# sistema_min.net
KiCad netlist of a schematic drawn in EAGLE
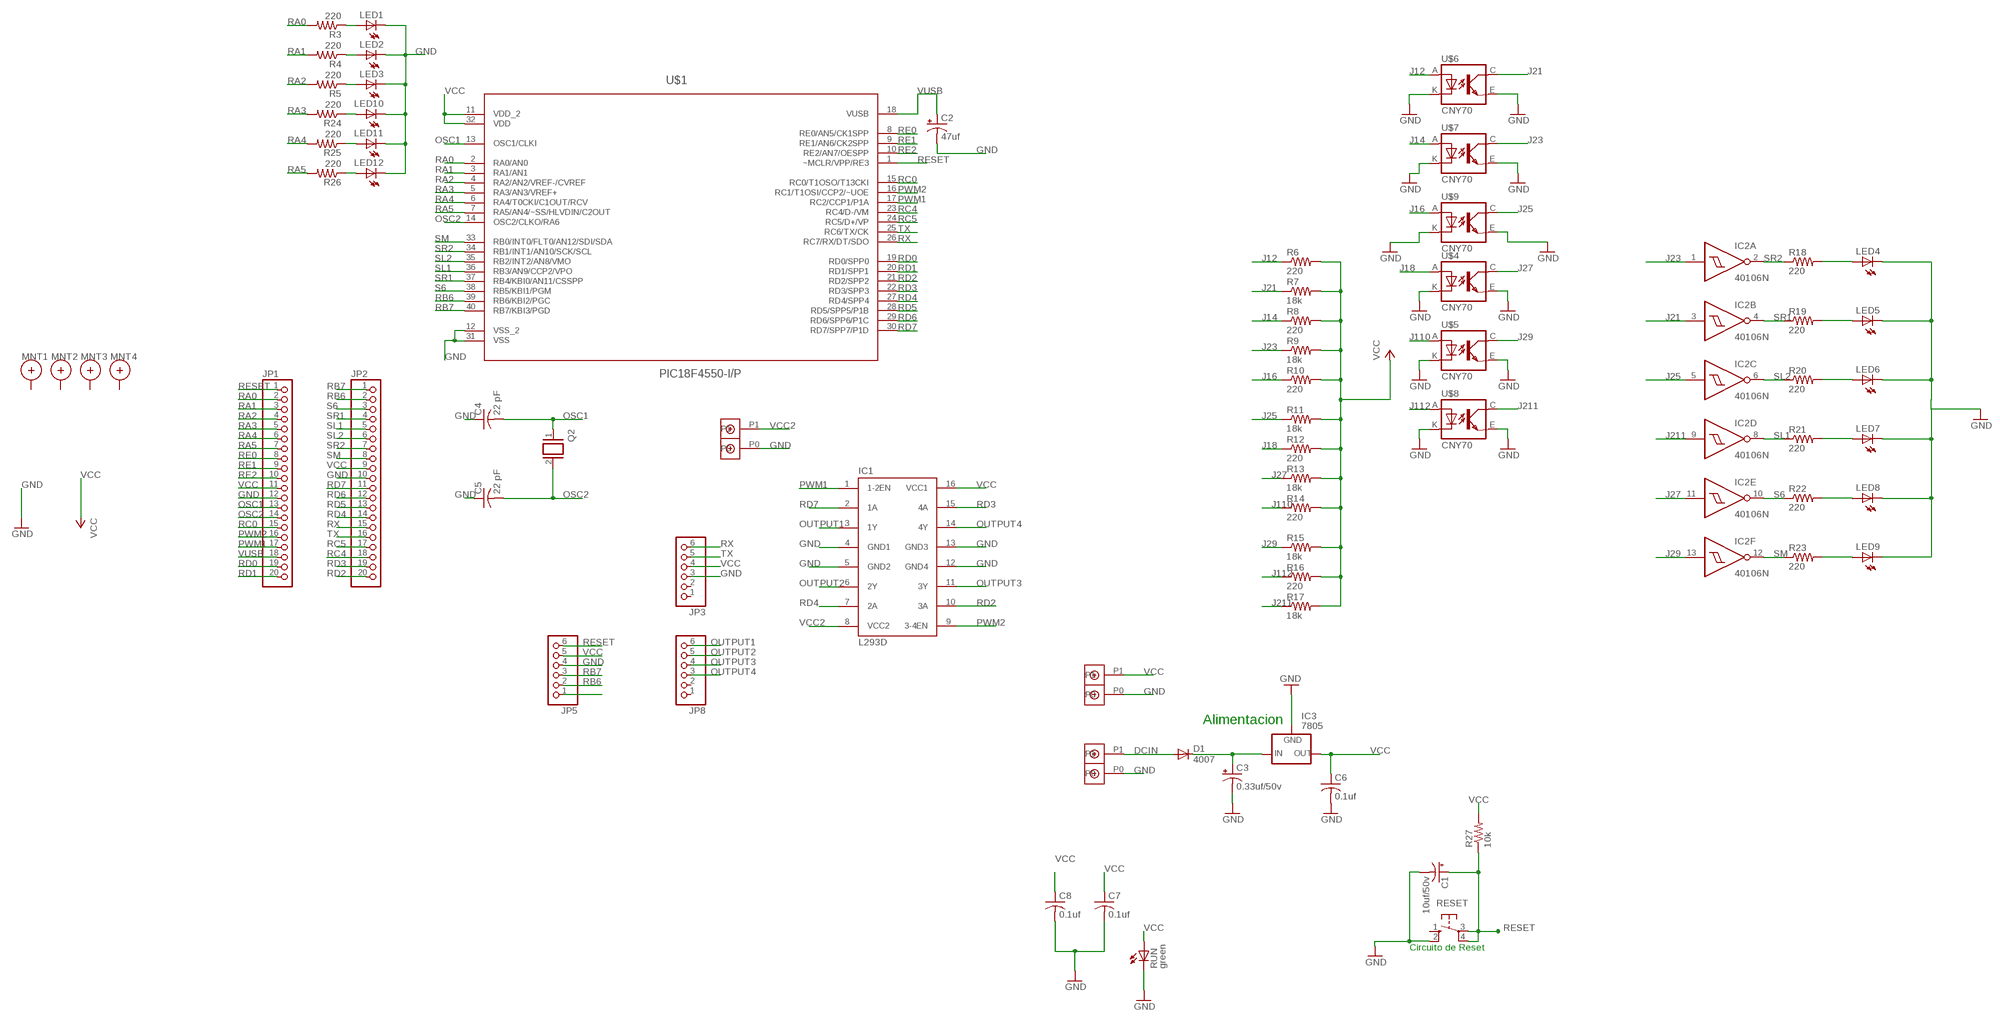
[diagram p0: schematic, sheet 1]

(export (version "E")
  (design (tool "Eeschema 10.0.6"))
  (components
    (comp (ref "C1")
      (value "10uf/50v")
      (footprint "eagle-import:153CLV-0505")
      (libsource (lib "eagle-import") (part "CPOL-US153CLV-0505"))
    )
    (comp (ref "C2")
      (value "47uf")
      (footprint "eagle-import:153CLV-0605")
      (libsource (lib "eagle-import") (part "CPOL-US153CLV-0605"))
    )
    (comp (ref "C3")
      (value "0.33uf/50v")
      (footprint "eagle-import:153CLV-0405")
      (libsource (lib "eagle-import") (part "CPOL-US153CLV-0405"))
    )
    (comp (ref "C4")
      (value "22 pF")
      (footprint "eagle-import:C1206")
      (libsource (lib "eagle-import") (part "C-USC1206"))
    )
    (comp (ref "C5")
      (value "22 pF")
      (footprint "eagle-import:C1206")
      (libsource (lib "eagle-import") (part "C-USC1206"))
    )
    (comp (ref "C6")
      (value "0.1uf")
      (footprint "eagle-import:C1206")
      (libsource (lib "eagle-import") (part "C-USC1206"))
    )
    (comp (ref "C7")
      (value "0.1uf")
      (footprint "eagle-import:C1206")
      (libsource (lib "eagle-import") (part "C-USC1206"))
    )
    (comp (ref "C8")
      (value "0.1uf")
      (footprint "eagle-import:C1206")
      (libsource (lib "eagle-import") (part "C-USC1206"))
    )
    (comp (ref "D1")
      (value "4007")
      (footprint "eagle-import:DO35-7")
      (libsource (lib "eagle-import") (part "1N4148DO35-7"))
    )
    (comp (ref "IC1")
      (value "L293D")
      (footprint "eagle-import:DIL16")
      (libsource (lib "eagle-import") (part "L293D"))
    )
    (comp (ref "IC2")
      (value "40106N")
      (footprint "eagle-import:DIL14")
      (libsource (lib "eagle-import") (part "40106N"))
    )
    (comp (ref "IC3")
      (value "7805")
      (footprint "eagle-import:79XXS")
      (libsource (lib "eagle-import") (part "79XXS"))
    )
    (comp (ref "JP1")
      (value "PINHD-1X20")
      (footprint "eagle-import:1X20")
      (libsource (lib "eagle-import") (part "PINHD-1X20"))
    )
    (comp (ref "JP2")
      (value "PINHD-1X20")
      (footprint "eagle-import:1X20")
      (libsource (lib "eagle-import") (part "PINHD-1X20"))
    )
    (comp (ref "JP3")
      (value "PINHD-1X6")
      (footprint "eagle-import:1X06")
      (libsource (lib "eagle-import") (part "PINHD-1X6"))
    )
    (comp (ref "JP5")
      (value "PINHD-1X6")
      (footprint "eagle-import:1X06")
      (libsource (lib "eagle-import") (part "PINHD-1X6"))
    )
    (comp (ref "JP8")
      (value "PINHD-1X6")
      (footprint "eagle-import:1X06")
      (libsource (lib "eagle-import") (part "PINHD-1X6"))
    )
    (comp (ref "LED1")
      (value "LEDCHIPLED_1206")
      (footprint "eagle-import:CHIPLED_1206")
      (libsource (lib "eagle-import") (part "LEDCHIPLED_1206"))
    )
    (comp (ref "LED2")
      (value "LEDCHIPLED_1206")
      (footprint "eagle-import:CHIPLED_1206")
      (libsource (lib "eagle-import") (part "LEDCHIPLED_1206"))
    )
    (comp (ref "LED3")
      (value "LEDCHIPLED_1206")
      (footprint "eagle-import:CHIPLED_1206")
      (libsource (lib "eagle-import") (part "LEDCHIPLED_1206"))
    )
    (comp (ref "LED4")
      (value "LEDCHIPLED_1206")
      (footprint "eagle-import:CHIPLED_1206")
      (libsource (lib "eagle-import") (part "LEDCHIPLED_1206"))
    )
    (comp (ref "LED5")
      (value "LEDCHIPLED_1206")
      (footprint "eagle-import:CHIPLED_1206")
      (libsource (lib "eagle-import") (part "LEDCHIPLED_1206"))
    )
    (comp (ref "LED6")
      (value "LEDCHIPLED_1206")
      (footprint "eagle-import:CHIPLED_1206")
      (libsource (lib "eagle-import") (part "LEDCHIPLED_1206"))
    )
    (comp (ref "LED7")
      (value "LEDCHIPLED_1206")
      (footprint "eagle-import:CHIPLED_1206")
      (libsource (lib "eagle-import") (part "LEDCHIPLED_1206"))
    )
    (comp (ref "LED8")
      (value "LEDCHIPLED_1206")
      (footprint "eagle-import:CHIPLED_1206")
      (libsource (lib "eagle-import") (part "LEDCHIPLED_1206"))
    )
    (comp (ref "LED9")
      (value "LEDCHIPLED_1206")
      (footprint "eagle-import:CHIPLED_1206")
      (libsource (lib "eagle-import") (part "LEDCHIPLED_1206"))
    )
    (comp (ref "LED10")
      (value "LEDCHIPLED_1206")
      (footprint "eagle-import:CHIPLED_1206")
      (libsource (lib "eagle-import") (part "LEDCHIPLED_1206"))
    )
    (comp (ref "LED11")
      (value "LEDCHIPLED_1206")
      (footprint "eagle-import:CHIPLED_1206")
      (libsource (lib "eagle-import") (part "LEDCHIPLED_1206"))
    )
    (comp (ref "LED12")
      (value "LEDCHIPLED_1206")
      (footprint "eagle-import:CHIPLED_1206")
      (libsource (lib "eagle-import") (part "LEDCHIPLED_1206"))
    )
    (comp (ref "MNT1")
      (value "HOLE_MNT_0.135")
      (footprint "eagle-import:HOLE_MNT_#5-40")
      (libsource (lib "eagle-import") (part "HOLE_MNT_0.135"))
    )
    (comp (ref "MNT2")
      (value "HOLE_MNT_0.135")
      (footprint "eagle-import:HOLE_MNT_#5-40")
      (libsource (lib "eagle-import") (part "HOLE_MNT_0.135"))
    )
    (comp (ref "MNT3")
      (value "HOLE_MNT_0.135")
      (footprint "eagle-import:HOLE_MNT_#5-40")
      (libsource (lib "eagle-import") (part "HOLE_MNT_0.135"))
    )
    (comp (ref "MNT4")
      (value "HOLE_MNT_0.135")
      (footprint "eagle-import:HOLE_MNT_#5-40")
      (libsource (lib "eagle-import") (part "HOLE_MNT_0.135"))
    )
    (comp (ref "Q2")
      (value "XTAL/S")
      (footprint "eagle-import:QS")
      (libsource (lib "eagle-import") (part "XTAL/S"))
    )
    (comp (ref "R3")
      (value "220")
      (footprint "eagle-import:M1206")
      (libsource (lib "eagle-import") (part "R-US_M1206"))
    )
    (comp (ref "R4")
      (value "220")
      (footprint "eagle-import:M1206")
      (libsource (lib "eagle-import") (part "R-US_M1206"))
    )
    (comp (ref "R5")
      (value "220")
      (footprint "eagle-import:M1206")
      (libsource (lib "eagle-import") (part "R-US_M1206"))
    )
    (comp (ref "R6")
      (value "220")
      (footprint "eagle-import:M1206")
      (libsource (lib "eagle-import") (part "R-US_M1206"))
    )
    (comp (ref "R7")
      (value "18k")
      (footprint "eagle-import:M1206")
      (libsource (lib "eagle-import") (part "R-US_M1206"))
    )
    (comp (ref "R8")
      (value "220")
      (footprint "eagle-import:M1206")
      (libsource (lib "eagle-import") (part "R-US_M1206"))
    )
    (comp (ref "R9")
      (value "18k")
      (footprint "eagle-import:M1206")
      (libsource (lib "eagle-import") (part "R-US_M1206"))
    )
    (comp (ref "R10")
      (value "220")
      (footprint "eagle-import:M1206")
      (libsource (lib "eagle-import") (part "R-US_M1206"))
    )
    (comp (ref "R11")
      (value "18k")
      (footprint "eagle-import:M1206")
      (libsource (lib "eagle-import") (part "R-US_M1206"))
    )
    (comp (ref "R12")
      (value "220")
      (footprint "eagle-import:M1206")
      (libsource (lib "eagle-import") (part "R-US_M1206"))
    )
    (comp (ref "R13")
      (value "18k")
      (footprint "eagle-import:M1206")
      (libsource (lib "eagle-import") (part "R-US_M1206"))
    )
    (comp (ref "R14")
      (value "220")
      (footprint "eagle-import:M1206")
      (libsource (lib "eagle-import") (part "R-US_M1206"))
    )
    (comp (ref "R15")
      (value "18k")
      (footprint "eagle-import:M1206")
      (libsource (lib "eagle-import") (part "R-US_M1206"))
    )
    (comp (ref "R16")
      (value "220")
      (footprint "eagle-import:M1206")
      (libsource (lib "eagle-import") (part "R-US_M1206"))
    )
    (comp (ref "R17")
      (value "18k")
      (footprint "eagle-import:M1206")
      (libsource (lib "eagle-import") (part "R-US_M1206"))
    )
    (comp (ref "R18")
      (value "220")
      (footprint "eagle-import:M1206")
      (libsource (lib "eagle-import") (part "R-US_M1206"))
    )
    (comp (ref "R19")
      (value "220")
      (footprint "eagle-import:M1206")
      (libsource (lib "eagle-import") (part "R-US_M1206"))
    )
    (comp (ref "R20")
      (value "220")
      (footprint "eagle-import:M1206")
      (libsource (lib "eagle-import") (part "R-US_M1206"))
    )
    (comp (ref "R21")
      (value "220")
      (footprint "eagle-import:M1206")
      (libsource (lib "eagle-import") (part "R-US_M1206"))
    )
    (comp (ref "R22")
      (value "220")
      (footprint "eagle-import:M1206")
      (libsource (lib "eagle-import") (part "R-US_M1206"))
    )
    (comp (ref "R23")
      (value "220")
      (footprint "eagle-import:M1206")
      (libsource (lib "eagle-import") (part "R-US_M1206"))
    )
    (comp (ref "R24")
      (value "220")
      (footprint "eagle-import:M1206")
      (libsource (lib "eagle-import") (part "R-US_M1206"))
    )
    (comp (ref "R25")
      (value "220")
      (footprint "eagle-import:M1206")
      (libsource (lib "eagle-import") (part "R-US_M1206"))
    )
    (comp (ref "R26")
      (value "220")
      (footprint "eagle-import:M1206")
      (libsource (lib "eagle-import") (part "R-US_M1206"))
    )
    (comp (ref "R27")
      (value "10k")
      (footprint "eagle-import:R1206")
      (libsource (lib "eagle-import") (part "R-US_R1206"))
    )
    (comp (ref "RESET")
      (value "10-XX")
      (footprint "eagle-import:B3F-10XX")
      (fields (field (name "MPN") "B3F-1000"))
      (libsource (lib "eagle-import") (part "10-XX"))
    )
    (comp (ref "RUN")
      (value "green")
      (footprint "eagle-import:SML1206")
      (libsource (lib "eagle-import") (part "LEDSML1206"))
    )
    (comp (ref "U$1")
      (value "PIC18F4550-I/P")
      (footprint "eagle-import:DIP254P1524X635-40")
      (libsource (lib "eagle-import") (part "PIC18F4550-I/P"))
    )
    (comp (ref "U$2")
      (value "DBCONN-1X2")
      (footprint "eagle-import:DBCONN-1X2")
      (libsource (lib "eagle-import") (part "DBCONN-1X2"))
    )
    (comp (ref "U$3")
      (value "DBCONN-1X2")
      (footprint "eagle-import:DBCONN-1X2")
      (libsource (lib "eagle-import") (part "DBCONN-1X2"))
    )
    (comp (ref "U$4")
      (value "CNY70")
      (footprint "eagle-import:4")
      (libsource (lib "eagle-import") (part "CNY70"))
    )
    (comp (ref "U$5")
      (value "CNY70")
      (footprint "eagle-import:4")
      (libsource (lib "eagle-import") (part "CNY70"))
    )
    (comp (ref "U$6")
      (value "CNY70")
      (footprint "eagle-import:4")
      (libsource (lib "eagle-import") (part "CNY70"))
    )
    (comp (ref "U$7")
      (value "CNY70")
      (footprint "eagle-import:4")
      (libsource (lib "eagle-import") (part "CNY70"))
    )
    (comp (ref "U$8")
      (value "CNY70")
      (footprint "eagle-import:4")
      (libsource (lib "eagle-import") (part "CNY70"))
    )
    (comp (ref "U$9")
      (value "CNY70")
      (footprint "eagle-import:4")
      (libsource (lib "eagle-import") (part "CNY70"))
    )
    (comp (ref "U$10")
      (value "DBCONN-1X2")
      (footprint "eagle-import:DBCONN-1X2")
      (libsource (lib "eagle-import") (part "DBCONN-1X2"))
    )
  )
  (nets
    (net (code "1") (name "/DCIN") (class "Default")
      (node (ref "D1") (pin "A") (pinfunction "A_A") (pintype "passive"))
      (node (ref "U$2") (pin "P1") (pinfunction "P1_P1") (pintype "bidirectional"))
    )
    (net (code "2") (name "/J12") (class "Default")
      (node (ref "R6") (pin "1") (pinfunction "1_1") (pintype "passive"))
      (node (ref "U$6") (pin "A") (pinfunction "A_A") (pintype "passive"))
    )
    (net (code "3") (name "/J14") (class "Default")
      (node (ref "R8") (pin "1") (pinfunction "1_1") (pintype "passive"))
      (node (ref "U$7") (pin "A") (pinfunction "A_A") (pintype "passive"))
    )
    (net (code "4") (name "/J16") (class "Default")
      (node (ref "R10") (pin "1") (pinfunction "1_1") (pintype "passive"))
      (node (ref "U$9") (pin "A") (pinfunction "A_A") (pintype "passive"))
    )
    (net (code "5") (name "/J18") (class "Default")
      (node (ref "R12") (pin "1") (pinfunction "1_1") (pintype "passive"))
      (node (ref "U$4") (pin "A") (pinfunction "A_A") (pintype "passive"))
    )
    (net (code "6") (name "/J21") (class "Default")
      (node (ref "IC2") (pin "3") (pinfunction "I_3") (pintype "input"))
      (node (ref "R7") (pin "1") (pinfunction "1_1") (pintype "passive"))
      (node (ref "U$6") (pin "C") (pinfunction "COL_C") (pintype "passive"))
    )
    (net (code "7") (name "/J23") (class "Default")
      (node (ref "IC2") (pin "1") (pinfunction "I_1") (pintype "input"))
      (node (ref "R9") (pin "1") (pinfunction "1_1") (pintype "passive"))
      (node (ref "U$7") (pin "C") (pinfunction "COL_C") (pintype "passive"))
    )
    (net (code "8") (name "/J25") (class "Default")
      (node (ref "IC2") (pin "5") (pinfunction "I_5") (pintype "input"))
      (node (ref "R11") (pin "1") (pinfunction "1_1") (pintype "passive"))
      (node (ref "U$9") (pin "C") (pinfunction "COL_C") (pintype "passive"))
    )
    (net (code "9") (name "/J27") (class "Default")
      (node (ref "IC2") (pin "11") (pinfunction "I_11") (pintype "input"))
      (node (ref "R13") (pin "1") (pinfunction "1_1") (pintype "passive"))
      (node (ref "U$4") (pin "C") (pinfunction "COL_C") (pintype "passive"))
    )
    (net (code "10") (name "/J29") (class "Default")
      (node (ref "IC2") (pin "13") (pinfunction "I_13") (pintype "input"))
      (node (ref "R15") (pin "1") (pinfunction "1_1") (pintype "passive"))
      (node (ref "U$5") (pin "C") (pinfunction "COL_C") (pintype "passive"))
    )
    (net (code "11") (name "/J110") (class "Default")
      (node (ref "R14") (pin "1") (pinfunction "1_1") (pintype "passive"))
      (node (ref "U$5") (pin "A") (pinfunction "A_A") (pintype "passive"))
    )
    (net (code "12") (name "/J112") (class "Default")
      (node (ref "R16") (pin "1") (pinfunction "1_1") (pintype "passive"))
      (node (ref "U$8") (pin "A") (pinfunction "A_A") (pintype "passive"))
    )
    (net (code "13") (name "/J211") (class "Default")
      (node (ref "IC2") (pin "9") (pinfunction "I_9") (pintype "input"))
      (node (ref "R17") (pin "1") (pinfunction "1_1") (pintype "passive"))
      (node (ref "U$8") (pin "C") (pinfunction "COL_C") (pintype "passive"))
    )
    (net (code "14") (name "/OSC1") (class "Default")
      (node (ref "C4") (pin "2") (pinfunction "2_2") (pintype "passive"))
      (node (ref "JP1") (pin "13") (pinfunction "13_13") (pintype "passive"))
      (node (ref "Q2") (pin "1") (pinfunction "1_1") (pintype "passive"))
      (node (ref "U$1") (pin "13") (pinfunction "OSC1/CLKI_13") (pintype "input"))
    )
    (net (code "15") (name "/OSC2") (class "Default")
      (node (ref "C5") (pin "2") (pinfunction "2_2") (pintype "passive"))
      (node (ref "JP1") (pin "14") (pinfunction "14_14") (pintype "passive"))
      (node (ref "Q2") (pin "2") (pinfunction "2_2") (pintype "passive"))
      (node (ref "U$1") (pin "14") (pinfunction "OSC2/CLKO/RA6_14") (pintype "bidirectional"))
    )
    (net (code "16") (name "/OUTPUT1") (class "Default")
      (node (ref "IC1") (pin "3") (pinfunction "1Y_3") (pintype "output"))
      (node (ref "JP8") (pin "6") (pinfunction "6_6") (pintype "passive"))
    )
    (net (code "17") (name "/OUTPUT2") (class "Default")
      (node (ref "IC1") (pin "6") (pinfunction "2Y_6") (pintype "output"))
      (node (ref "JP8") (pin "5") (pinfunction "5_5") (pintype "passive"))
    )
    (net (code "18") (name "/OUTPUT3") (class "Default")
      (node (ref "IC1") (pin "11") (pinfunction "3Y_11") (pintype "output"))
      (node (ref "JP8") (pin "4") (pinfunction "4_4") (pintype "passive"))
    )
    (net (code "19") (name "/OUTPUT4") (class "Default")
      (node (ref "IC1") (pin "14") (pinfunction "4Y_14") (pintype "output"))
      (node (ref "JP8") (pin "3") (pinfunction "3_3") (pintype "passive"))
    )
    (net (code "20") (name "/PWM1") (class "Default")
      (node (ref "IC1") (pin "1") (pinfunction "1-2EN_1") (pintype "input"))
      (node (ref "JP1") (pin "17") (pinfunction "17_17") (pintype "passive"))
      (node (ref "U$1") (pin "17") (pinfunction "RC2/CCP1/P1A_17") (pintype "bidirectional"))
    )
    (net (code "21") (name "/PWM2") (class "Default")
      (node (ref "IC1") (pin "9") (pinfunction "3-4EN_9") (pintype "input"))
      (node (ref "JP1") (pin "16") (pinfunction "16_16") (pintype "passive"))
      (node (ref "U$1") (pin "16") (pinfunction "RC1/T1OSI/CCP2/~{UOE}_16") (pintype "bidirectional"))
    )
    (net (code "22") (name "/RA0") (class "Default")
      (node (ref "JP1") (pin "2") (pinfunction "2_2") (pintype "passive"))
      (node (ref "R3") (pin "2") (pinfunction "2_2") (pintype "passive"))
      (node (ref "U$1") (pin "2") (pinfunction "RA0/AN0_2") (pintype "bidirectional"))
    )
    (net (code "23") (name "/RA1") (class "Default")
      (node (ref "JP1") (pin "3") (pinfunction "3_3") (pintype "passive"))
      (node (ref "R4") (pin "2") (pinfunction "2_2") (pintype "passive"))
      (node (ref "U$1") (pin "3") (pinfunction "RA1/AN1_3") (pintype "bidirectional"))
    )
    (net (code "24") (name "/RA2") (class "Default")
      (node (ref "JP1") (pin "4") (pinfunction "4_4") (pintype "passive"))
      (node (ref "R5") (pin "2") (pinfunction "2_2") (pintype "passive"))
      (node (ref "U$1") (pin "4") (pinfunction "RA2/AN2/VREF-/CVREF_4") (pintype "bidirectional"))
    )
    (net (code "25") (name "/RA3") (class "Default")
      (node (ref "JP1") (pin "5") (pinfunction "5_5") (pintype "passive"))
      (node (ref "R24") (pin "2") (pinfunction "2_2") (pintype "passive"))
      (node (ref "U$1") (pin "5") (pinfunction "RA3/AN3/VREF+_5") (pintype "bidirectional"))
    )
    (net (code "26") (name "/RA4") (class "Default")
      (node (ref "JP1") (pin "6") (pinfunction "6_6") (pintype "passive"))
      (node (ref "R25") (pin "2") (pinfunction "2_2") (pintype "passive"))
      (node (ref "U$1") (pin "6") (pinfunction "RA4/T0CKI/C1OUT/RCV_6") (pintype "bidirectional"))
    )
    (net (code "27") (name "/RA5") (class "Default")
      (node (ref "JP1") (pin "7") (pinfunction "7_7") (pintype "passive"))
      (node (ref "R26") (pin "2") (pinfunction "2_2") (pintype "passive"))
      (node (ref "U$1") (pin "7") (pinfunction "RA5/AN4/~{SS/HLVDIN/C2OUT}_7") (pintype "bidirectional"))
    )
    (net (code "28") (name "/RB6") (class "Default")
      (node (ref "JP2") (pin "2") (pinfunction "2_2") (pintype "passive"))
      (node (ref "JP5") (pin "2") (pinfunction "2_2") (pintype "passive"))
      (node (ref "U$1") (pin "39") (pinfunction "RB6/KBI2/PGC_39") (pintype "bidirectional"))
    )
    (net (code "29") (name "/RB7") (class "Default")
      (node (ref "JP2") (pin "1") (pinfunction "1_1") (pintype "passive"))
      (node (ref "JP5") (pin "3") (pinfunction "3_3") (pintype "passive"))
      (node (ref "U$1") (pin "40") (pinfunction "RB7/KBI3/PGD_40") (pintype "bidirectional"))
    )
    (net (code "30") (name "/RC0") (class "Default")
      (node (ref "JP1") (pin "15") (pinfunction "15_15") (pintype "passive"))
      (node (ref "U$1") (pin "15") (pinfunction "RC0/T1OSO/T13CKI_15") (pintype "bidirectional"))
    )
    (net (code "31") (name "/RC4") (class "Default")
      (node (ref "JP2") (pin "18") (pinfunction "18_18") (pintype "passive"))
      (node (ref "U$1") (pin "23") (pinfunction "RC4/D-/VM_23") (pintype "bidirectional"))
    )
    (net (code "32") (name "/RC5") (class "Default")
      (node (ref "JP2") (pin "17") (pinfunction "17_17") (pintype "passive"))
      (node (ref "U$1") (pin "24") (pinfunction "RC5/D+/VP_24") (pintype "bidirectional"))
    )
    (net (code "33") (name "/RD0") (class "Default")
      (node (ref "JP1") (pin "19") (pinfunction "19_19") (pintype "passive"))
      (node (ref "U$1") (pin "19") (pinfunction "RD0/SPP0_19") (pintype "bidirectional"))
    )
    (net (code "34") (name "/RD1") (class "Default")
      (node (ref "JP1") (pin "20") (pinfunction "20_20") (pintype "passive"))
      (node (ref "U$1") (pin "20") (pinfunction "RD1/SPP1_20") (pintype "bidirectional"))
    )
    (net (code "35") (name "/RD2") (class "Default")
      (node (ref "IC1") (pin "10") (pinfunction "3A_10") (pintype "input"))
      (node (ref "JP2") (pin "20") (pinfunction "20_20") (pintype "passive"))
      (node (ref "U$1") (pin "21") (pinfunction "RD2/SPP2_21") (pintype "bidirectional"))
    )
    (net (code "36") (name "/RD3") (class "Default")
      (node (ref "IC1") (pin "15") (pinfunction "4A_15") (pintype "input"))
      (node (ref "JP2") (pin "19") (pinfunction "19_19") (pintype "passive"))
      (node (ref "U$1") (pin "22") (pinfunction "RD3/SPP3_22") (pintype "bidirectional"))
    )
    (net (code "37") (name "/RD4") (class "Default")
      (node (ref "IC1") (pin "7") (pinfunction "2A_7") (pintype "input"))
      (node (ref "JP2") (pin "14") (pinfunction "14_14") (pintype "passive"))
      (node (ref "U$1") (pin "27") (pinfunction "RD4/SPP4_27") (pintype "bidirectional"))
    )
    (net (code "38") (name "/RD5") (class "Default")
      (node (ref "JP2") (pin "13") (pinfunction "13_13") (pintype "passive"))
      (node (ref "U$1") (pin "28") (pinfunction "RD5/SPP5/P1B_28") (pintype "bidirectional"))
    )
    (net (code "39") (name "/RD6") (class "Default")
      (node (ref "JP2") (pin "12") (pinfunction "12_12") (pintype "passive"))
      (node (ref "U$1") (pin "29") (pinfunction "RD6/SPP6/P1C_29") (pintype "bidirectional"))
    )
    (net (code "40") (name "/RD7") (class "Default")
      (node (ref "IC1") (pin "2") (pinfunction "1A_2") (pintype "input"))
      (node (ref "JP2") (pin "11") (pinfunction "11_11") (pintype "passive"))
      (node (ref "U$1") (pin "30") (pinfunction "RD7/SPP7/P1D_30") (pintype "bidirectional"))
    )
    (net (code "41") (name "/RE0") (class "Default")
      (node (ref "JP1") (pin "8") (pinfunction "8_8") (pintype "passive"))
      (node (ref "U$1") (pin "8") (pinfunction "RE0/AN5/CK1SPP_8") (pintype "bidirectional"))
    )
    (net (code "42") (name "/RE1") (class "Default")
      (node (ref "JP1") (pin "9") (pinfunction "9_9") (pintype "passive"))
      (node (ref "U$1") (pin "9") (pinfunction "RE1/AN6/CK2SPP_9") (pintype "bidirectional"))
    )
    (net (code "43") (name "/RE2") (class "Default")
      (node (ref "JP1") (pin "10") (pinfunction "10_10") (pintype "passive"))
      (node (ref "U$1") (pin "10") (pinfunction "RE2/AN7/OESPP_10") (pintype "bidirectional"))
    )
    (net (code "44") (name "/RESET") (class "Default")
      (node (ref "C1") (pin "+") (pinfunction "+_+") (pintype "passive"))
      (node (ref "JP1") (pin "1") (pinfunction "1_1") (pintype "passive"))
      (node (ref "JP5") (pin "6") (pinfunction "6_6") (pintype "passive"))
      (node (ref "R27") (pin "1") (pinfunction "1_1") (pintype "passive"))
      (node (ref "RESET") (pin "3") (pinfunction "P_3") (pintype "passive"))
      (node (ref "RESET") (pin "4") (pinfunction "P1_4") (pintype "passive"))
      (node (ref "U$1") (pin "1") (pinfunction "~{MCLR/VPP/RE3}_1") (pintype "input"))
    )
    (net (code "45") (name "/RX") (class "Default")
      (node (ref "JP2") (pin "15") (pinfunction "15_15") (pintype "passive"))
      (node (ref "JP3") (pin "6") (pinfunction "6_6") (pintype "passive"))
      (node (ref "U$1") (pin "26") (pinfunction "RC7/RX/DT/SDO_26") (pintype "bidirectional"))
    )
    (net (code "46") (name "/S6") (class "Default")
      (node (ref "IC2") (pin "10") (pinfunction "O_10") (pintype "output"))
      (node (ref "JP2") (pin "3") (pinfunction "3_3") (pintype "passive"))
      (node (ref "R22") (pin "1") (pinfunction "1_1") (pintype "passive"))
      (node (ref "U$1") (pin "38") (pinfunction "RB5/KBI1/PGM_38") (pintype "bidirectional"))
    )
    (net (code "47") (name "/SL1") (class "Default")
      (node (ref "IC2") (pin "8") (pinfunction "O_8") (pintype "output"))
      (node (ref "JP2") (pin "5") (pinfunction "5_5") (pintype "passive"))
      (node (ref "R21") (pin "1") (pinfunction "1_1") (pintype "passive"))
      (node (ref "U$1") (pin "36") (pinfunction "RB3/AN9/CCP2/VPO_36") (pintype "bidirectional"))
    )
    (net (code "48") (name "/SL2") (class "Default")
      (node (ref "IC2") (pin "6") (pinfunction "O_6") (pintype "output"))
      (node (ref "JP2") (pin "6") (pinfunction "6_6") (pintype "passive"))
      (node (ref "R20") (pin "1") (pinfunction "1_1") (pintype "passive"))
      (node (ref "U$1") (pin "35") (pinfunction "RB2/INT2/AN8/VMO_35") (pintype "bidirectional"))
    )
    (net (code "49") (name "/SM") (class "Default")
      (node (ref "IC2") (pin "12") (pinfunction "O_12") (pintype "output"))
      (node (ref "JP2") (pin "8") (pinfunction "8_8") (pintype "passive"))
      (node (ref "R23") (pin "1") (pinfunction "1_1") (pintype "passive"))
      (node (ref "U$1") (pin "33") (pinfunction "RB0/INT0/FLT0/AN12/SDI/SDA_33") (pintype "bidirectional"))
    )
    (net (code "50") (name "/SR1") (class "Default")
      (node (ref "IC2") (pin "4") (pinfunction "O_4") (pintype "output"))
      (node (ref "JP2") (pin "4") (pinfunction "4_4") (pintype "passive"))
      (node (ref "R19") (pin "1") (pinfunction "1_1") (pintype "passive"))
      (node (ref "U$1") (pin "37") (pinfunction "RB4/KBI0/AN11/CSSPP_37") (pintype "bidirectional"))
    )
    (net (code "51") (name "/SR2") (class "Default")
      (node (ref "IC2") (pin "2") (pinfunction "O_2") (pintype "output"))
      (node (ref "JP2") (pin "7") (pinfunction "7_7") (pintype "passive"))
      (node (ref "R18") (pin "1") (pinfunction "1_1") (pintype "passive"))
      (node (ref "U$1") (pin "34") (pinfunction "RB1/INT1/AN10/SCK/SCL_34") (pintype "bidirectional"))
    )
    (net (code "52") (name "/TX") (class "Default")
      (node (ref "JP2") (pin "16") (pinfunction "16_16") (pintype "passive"))
      (node (ref "JP3") (pin "5") (pinfunction "5_5") (pintype "passive"))
      (node (ref "U$1") (pin "25") (pinfunction "RC6/TX/CK_25") (pintype "bidirectional"))
    )
    (net (code "53") (name "/VCC2") (class "Default")
      (node (ref "IC1") (pin "8") (pinfunction "VCC2_8") (pintype "power_in"))
      (node (ref "U$3") (pin "P1") (pinfunction "P1_P1") (pintype "bidirectional"))
    )
    (net (code "54") (name "/VUSB") (class "Default")
      (node (ref "C2") (pin "+") (pinfunction "+_+") (pintype "passive"))
      (node (ref "JP1") (pin "18") (pinfunction "18_18") (pintype "passive"))
      (node (ref "U$1") (pin "18") (pinfunction "VUSB_18") (pintype "bidirectional"))
    )
    (net (code "55") (name "GND") (class "Default")
      (node (ref "C1") (pin "-") (pinfunction "-_-") (pintype "passive"))
      (node (ref "C2") (pin "-") (pinfunction "-_-") (pintype "passive"))
      (node (ref "C3") (pin "-") (pinfunction "-_-") (pintype "passive"))
      (node (ref "C4") (pin "1") (pinfunction "1_1") (pintype "passive"))
      (node (ref "C5") (pin "1") (pinfunction "1_1") (pintype "passive"))
      (node (ref "C6") (pin "2") (pinfunction "2_2") (pintype "passive"))
      (node (ref "C7") (pin "2") (pinfunction "2_2") (pintype "passive"))
      (node (ref "C8") (pin "2") (pinfunction "2_2") (pintype "passive"))
      (node (ref "IC1") (pin "12") (pinfunction "GND4_12") (pintype "power_in"))
      (node (ref "IC1") (pin "13") (pinfunction "GND3_13") (pintype "power_in"))
      (node (ref "IC1") (pin "4") (pinfunction "GND1_4") (pintype "power_in"))
      (node (ref "IC1") (pin "5") (pinfunction "GND2_5") (pintype "power_in"))
      (node (ref "IC3") (pin "GND") (pinfunction "GND_GND") (pintype "input"))
      (node (ref "JP1") (pin "12") (pinfunction "12_12") (pintype "passive"))
      (node (ref "JP2") (pin "10") (pinfunction "10_10") (pintype "passive"))
      (node (ref "JP3") (pin "3") (pinfunction "3_3") (pintype "passive"))
      (node (ref "JP5") (pin "4") (pinfunction "4_4") (pintype "passive"))
      (node (ref "LED1") (pin "C") (pinfunction "C_C") (pintype "passive"))
      (node (ref "LED10") (pin "C") (pinfunction "C_C") (pintype "passive"))
      (node (ref "LED11") (pin "C") (pinfunction "C_C") (pintype "passive"))
      (node (ref "LED12") (pin "C") (pinfunction "C_C") (pintype "passive"))
      (node (ref "LED2") (pin "C") (pinfunction "C_C") (pintype "passive"))
      (node (ref "LED3") (pin "C") (pinfunction "C_C") (pintype "passive"))
      (node (ref "LED4") (pin "C") (pinfunction "C_C") (pintype "passive"))
      (node (ref "LED5") (pin "C") (pinfunction "C_C") (pintype "passive"))
      (node (ref "LED6") (pin "C") (pinfunction "C_C") (pintype "passive"))
      (node (ref "LED7") (pin "C") (pinfunction "C_C") (pintype "passive"))
      (node (ref "LED8") (pin "C") (pinfunction "C_C") (pintype "passive"))
      (node (ref "LED9") (pin "C") (pinfunction "C_C") (pintype "passive"))
      (node (ref "RESET") (pin "2") (pinfunction "S1_2") (pintype "passive"))
      (node (ref "RUN") (pin "C") (pinfunction "C_C") (pintype "passive"))
      (node (ref "U$1") (pin "12") (pinfunction "VSS_2_12") (pintype "power_in"))
      (node (ref "U$1") (pin "31") (pinfunction "VSS_31") (pintype "power_in"))
      (node (ref "U$10") (pin "P0") (pinfunction "P0_P0") (pintype "bidirectional"))
      (node (ref "U$2") (pin "P0") (pinfunction "P0_P0") (pintype "bidirectional"))
      (node (ref "U$3") (pin "P0") (pinfunction "P0_P0") (pintype "bidirectional"))
      (node (ref "U$4") (pin "E") (pinfunction "EMI_E") (pintype "passive"))
      (node (ref "U$4") (pin "K") (pinfunction "C_K") (pintype "passive"))
      (node (ref "U$5") (pin "E") (pinfunction "EMI_E") (pintype "passive"))
      (node (ref "U$5") (pin "K") (pinfunction "C_K") (pintype "passive"))
      (node (ref "U$6") (pin "E") (pinfunction "EMI_E") (pintype "passive"))
      (node (ref "U$6") (pin "K") (pinfunction "C_K") (pintype "passive"))
      (node (ref "U$7") (pin "E") (pinfunction "EMI_E") (pintype "passive"))
      (node (ref "U$7") (pin "K") (pinfunction "C_K") (pintype "passive"))
      (node (ref "U$8") (pin "E") (pinfunction "EMI_E") (pintype "passive"))
      (node (ref "U$8") (pin "K") (pinfunction "C_K") (pintype "passive"))
      (node (ref "U$9") (pin "E") (pinfunction "EMI_E") (pintype "passive"))
      (node (ref "U$9") (pin "K") (pinfunction "C_K") (pintype "passive"))
    )
    (net (code "56") (name "Net-(C3-Pad+)") (class "Default")
      (node (ref "C3") (pin "+") (pinfunction "+_+") (pintype "passive"))
      (node (ref "D1") (pin "C") (pinfunction "C_C") (pintype "passive"))
      (node (ref "IC3") (pin "IN") (pinfunction "IN_IN") (pintype "input"))
    )
    (net (code "57") (name "Net-(LED1-PadA)") (class "Default")
      (node (ref "LED1") (pin "A") (pinfunction "A_A") (pintype "passive"))
      (node (ref "R3") (pin "1") (pinfunction "1_1") (pintype "passive"))
    )
    (net (code "58") (name "Net-(LED2-PadA)") (class "Default")
      (node (ref "LED2") (pin "A") (pinfunction "A_A") (pintype "passive"))
      (node (ref "R4") (pin "1") (pinfunction "1_1") (pintype "passive"))
    )
    (net (code "59") (name "Net-(LED3-PadA)") (class "Default")
      (node (ref "LED3") (pin "A") (pinfunction "A_A") (pintype "passive"))
      (node (ref "R5") (pin "1") (pinfunction "1_1") (pintype "passive"))
    )
    (net (code "60") (name "Net-(LED4-PadA)") (class "Default")
      (node (ref "LED4") (pin "A") (pinfunction "A_A") (pintype "passive"))
      (node (ref "R18") (pin "2") (pinfunction "2_2") (pintype "passive"))
    )
    (net (code "61") (name "Net-(LED5-PadA)") (class "Default")
      (node (ref "LED5") (pin "A") (pinfunction "A_A") (pintype "passive"))
      (node (ref "R19") (pin "2") (pinfunction "2_2") (pintype "passive"))
    )
    (net (code "62") (name "Net-(LED6-PadA)") (class "Default")
      (node (ref "LED6") (pin "A") (pinfunction "A_A") (pintype "passive"))
      (node (ref "R20") (pin "2") (pinfunction "2_2") (pintype "passive"))
    )
    (net (code "63") (name "Net-(LED7-PadA)") (class "Default")
      (node (ref "LED7") (pin "A") (pinfunction "A_A") (pintype "passive"))
      (node (ref "R21") (pin "2") (pinfunction "2_2") (pintype "passive"))
    )
    (net (code "64") (name "Net-(LED8-PadA)") (class "Default")
      (node (ref "LED8") (pin "A") (pinfunction "A_A") (pintype "passive"))
      (node (ref "R22") (pin "2") (pinfunction "2_2") (pintype "passive"))
    )
    (net (code "65") (name "Net-(LED9-PadA)") (class "Default")
      (node (ref "LED9") (pin "A") (pinfunction "A_A") (pintype "passive"))
      (node (ref "R23") (pin "2") (pinfunction "2_2") (pintype "passive"))
    )
    (net (code "66") (name "Net-(LED10-PadA)") (class "Default")
      (node (ref "LED10") (pin "A") (pinfunction "A_A") (pintype "passive"))
      (node (ref "R24") (pin "1") (pinfunction "1_1") (pintype "passive"))
    )
    (net (code "67") (name "Net-(LED11-PadA)") (class "Default")
      (node (ref "LED11") (pin "A") (pinfunction "A_A") (pintype "passive"))
      (node (ref "R25") (pin "1") (pinfunction "1_1") (pintype "passive"))
    )
    (net (code "68") (name "Net-(LED12-PadA)") (class "Default")
      (node (ref "LED12") (pin "A") (pinfunction "A_A") (pintype "passive"))
      (node (ref "R26") (pin "1") (pinfunction "1_1") (pintype "passive"))
    )
    (net (code "69") (name "VCC") (class "Default")
      (node (ref "C6") (pin "1") (pinfunction "1_1") (pintype "passive"))
      (node (ref "C7") (pin "1") (pinfunction "1_1") (pintype "passive"))
      (node (ref "C8") (pin "1") (pinfunction "1_1") (pintype "passive"))
      (node (ref "IC1") (pin "16") (pinfunction "VCC1_16") (pintype "power_in"))
      (node (ref "IC3") (pin "OUT") (pinfunction "OUT_OUT") (pintype "passive"))
      (node (ref "JP1") (pin "11") (pinfunction "11_11") (pintype "passive"))
      (node (ref "JP2") (pin "9") (pinfunction "9_9") (pintype "passive"))
      (node (ref "JP3") (pin "4") (pinfunction "4_4") (pintype "passive"))
      (node (ref "JP5") (pin "5") (pinfunction "5_5") (pintype "passive"))
      (node (ref "R10") (pin "2") (pinfunction "2_2") (pintype "passive"))
      (node (ref "R11") (pin "2") (pinfunction "2_2") (pintype "passive"))
      (node (ref "R12") (pin "2") (pinfunction "2_2") (pintype "passive"))
      (node (ref "R13") (pin "2") (pinfunction "2_2") (pintype "passive"))
      (node (ref "R14") (pin "2") (pinfunction "2_2") (pintype "passive"))
      (node (ref "R15") (pin "2") (pinfunction "2_2") (pintype "passive"))
      (node (ref "R16") (pin "2") (pinfunction "2_2") (pintype "passive"))
      (node (ref "R17") (pin "2") (pinfunction "2_2") (pintype "passive"))
      (node (ref "R27") (pin "2") (pinfunction "2_2") (pintype "passive"))
      (node (ref "R6") (pin "2") (pinfunction "2_2") (pintype "passive"))
      (node (ref "R7") (pin "2") (pinfunction "2_2") (pintype "passive"))
      (node (ref "R8") (pin "2") (pinfunction "2_2") (pintype "passive"))
      (node (ref "R9") (pin "2") (pinfunction "2_2") (pintype "passive"))
      (node (ref "RUN") (pin "A") (pinfunction "A_A") (pintype "passive"))
      (node (ref "U$1") (pin "11") (pinfunction "VDD_2_11") (pintype "power_in"))
      (node (ref "U$1") (pin "32") (pinfunction "VDD_32") (pintype "power_in"))
      (node (ref "U$10") (pin "P1") (pinfunction "P1_P1") (pintype "bidirectional"))
    )
    (net (code "70") (name "unconnected-(JP3-Pad1)") (class "Default")
      (node (ref "JP3") (pin "1") (pinfunction "1_1") (pintype "passive"))
    )
    (net (code "71") (name "unconnected-(JP3-Pad2)") (class "Default")
      (node (ref "JP3") (pin "2") (pinfunction "2_2") (pintype "passive"))
    )
    (net (code "72") (name "unconnected-(JP5-Pad1)") (class "Default")
      (node (ref "JP5") (pin "1") (pinfunction "1_1") (pintype "passive"))
    )
    (net (code "73") (name "unconnected-(JP8-Pad1)") (class "Default")
      (node (ref "JP8") (pin "1") (pinfunction "1_1") (pintype "passive"))
    )
    (net (code "74") (name "unconnected-(JP8-Pad2)") (class "Default")
      (node (ref "JP8") (pin "2") (pinfunction "2_2") (pintype "passive"))
    )
    (net (code "75") (name "unconnected-(MNT1-1-PadP$1)") (class "Default")
      (node (ref "MNT1") (pin "P$1") (pinfunction "1_P$1") (pintype "bidirectional"))
    )
    (net (code "76") (name "unconnected-(MNT2-1-PadP$1)") (class "Default")
      (node (ref "MNT2") (pin "P$1") (pinfunction "1_P$1") (pintype "bidirectional"))
    )
    (net (code "77") (name "unconnected-(MNT3-1-PadP$1)") (class "Default")
      (node (ref "MNT3") (pin "P$1") (pinfunction "1_P$1") (pintype "bidirectional"))
    )
    (net (code "78") (name "unconnected-(MNT4-1-PadP$1)") (class "Default")
      (node (ref "MNT4") (pin "P$1") (pinfunction "1_P$1") (pintype "bidirectional"))
    )
    (net (code "79") (name "unconnected-(RESET-S-Pad1)") (class "Default")
      (node (ref "RESET") (pin "1") (pinfunction "S_1") (pintype "passive"))
    )
  )
)
